# MCU023_XDS110_Debug_Probe.net
KiCad netlist of a schematic drawn in Altium Designer
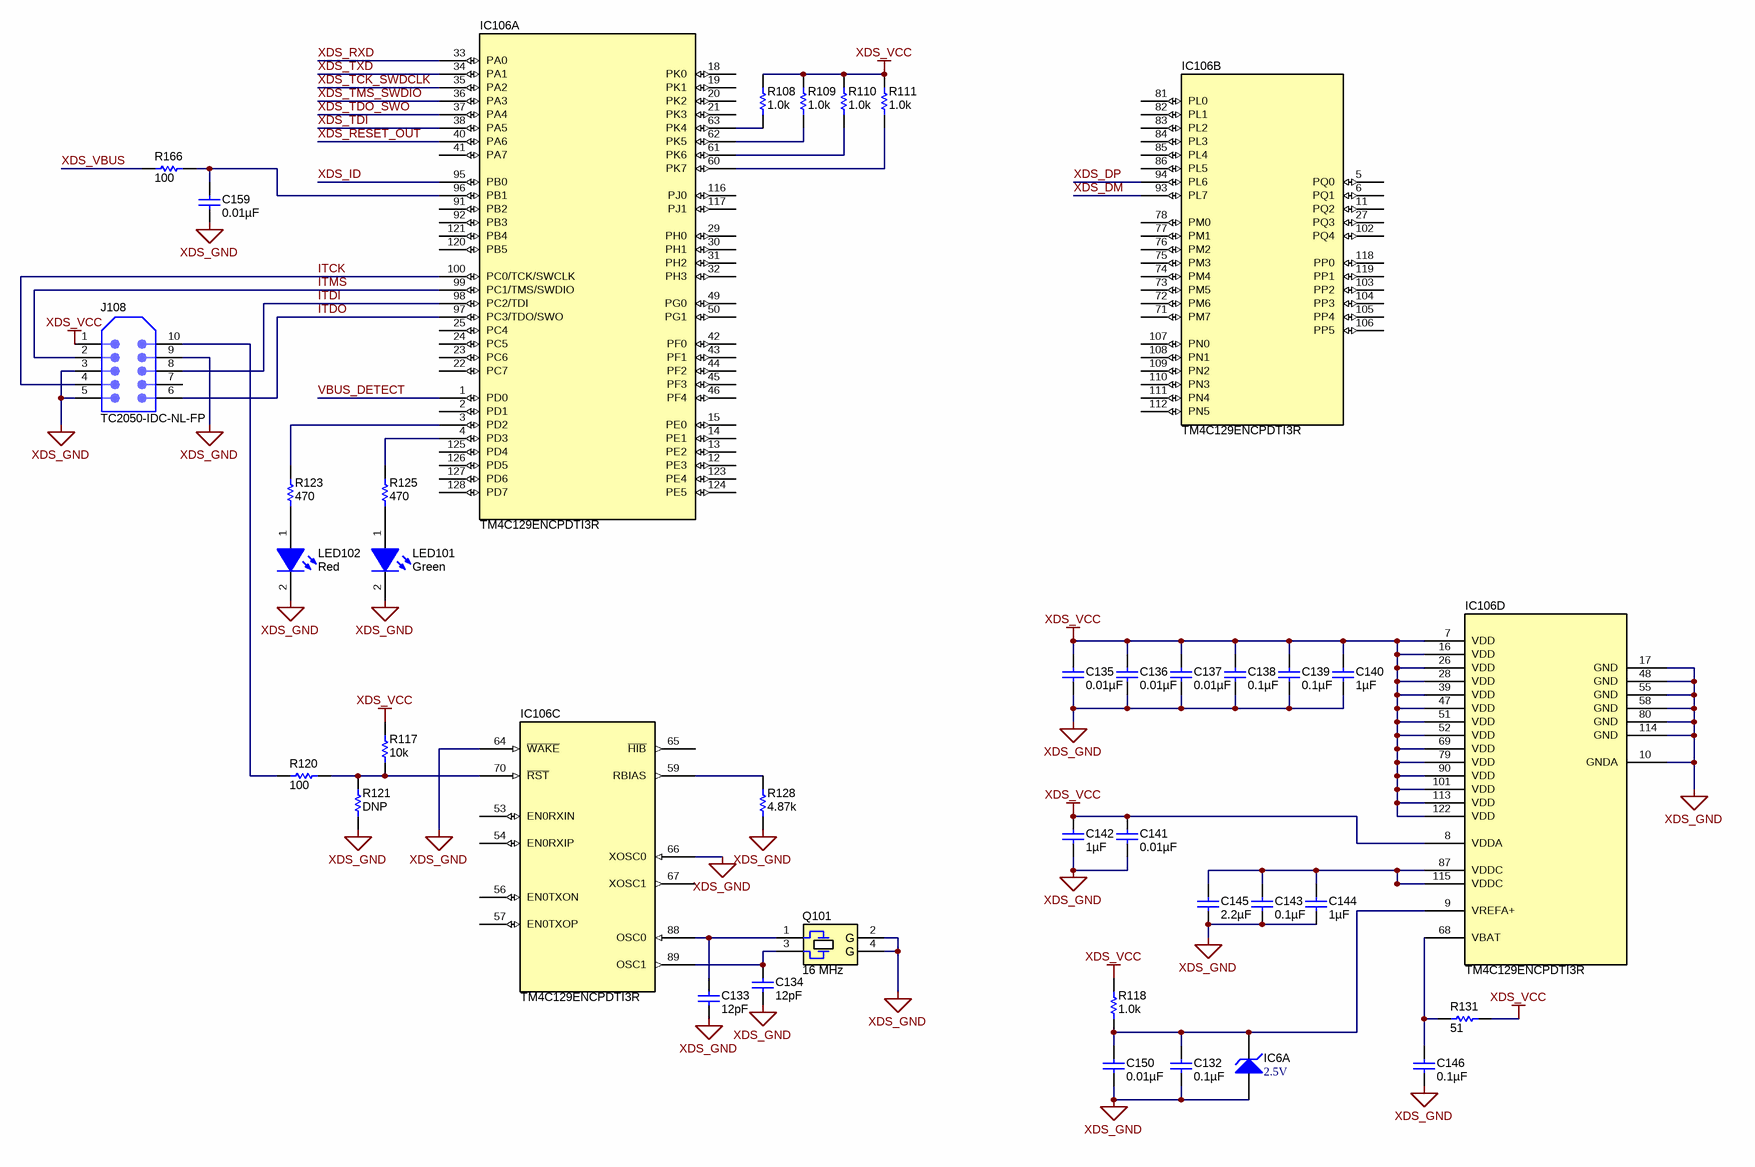
[diagram p0: MCU023_XDS110_Debug_Probe.SchDoc]

(export (version "E")
  (design (tool "Eeschema 10.0.6"))
  (components
    (comp (ref "C132")
      (value "GRM155R70J104KA01D")
      (footprint "0402")
      (description "CAP, CERM, 0.1 µF, 6.3 V, +/- 10%, X7R, 0402")
      (fields
        (field (name "VALUEDISPLAYED") "0.1µF")
        (field (name "MANUFACTURER") "MuRata")
        (field (name "PUBLISHER") "Texas Instruments")
      )
      (libsource (lib "Capacitor_Ceramic") (part "GRM155R70J104KA01D"))
    )
    (comp (ref "C133")
      (value "GRM1555C1H120JA01D")
      (footprint "0402")
      (description "CAP, CERM, 12 pF, 50 V, +/- 5%, C0G/NP0, 0402")
      (fields
        (field (name "VALUEDISPLAYED") "12pF")
        (field (name "MANUFACTURER") "MuRata")
        (field (name "PUBLISHER") "Texas Instruments")
      )
      (libsource (lib "Capacitor_Ceramic") (part "GRM1555C1H120JA01D"))
    )
    (comp (ref "C134")
      (value "GRM1555C1H120JA01D")
      (footprint "0402")
      (description "CAP, CERM, 12 pF, 50 V, +/- 5%, C0G/NP0, 0402")
      (fields
        (field (name "VALUEDISPLAYED") "12pF")
        (field (name "MANUFACTURER") "MuRata")
        (field (name "PUBLISHER") "Texas Instruments")
      )
      (libsource (lib "Capacitor_Ceramic") (part "GRM1555C1H120JA01D"))
    )
    (comp (ref "C135")
      (value "GRM155R71E103KA01D")
      (footprint "0402")
      (description "CAP, CERM, 0.01 µF, 25 V, +/- 10%, X7R, 0402")
      (fields
        (field (name "VALUEDISPLAYED") "0.01µF")
        (field (name "MANUFACTURER") "MuRata")
        (field (name "PUBLISHER") "Texas Instruments")
      )
      (libsource (lib "Capacitor_Ceramic") (part "GRM155R71E103KA01D"))
    )
    (comp (ref "C136")
      (value "GRM155R71E103KA01D")
      (footprint "0402")
      (description "CAP, CERM, 0.01 µF, 25 V, +/- 10%, X7R, 0402")
      (fields
        (field (name "VALUEDISPLAYED") "0.01µF")
        (field (name "MANUFACTURER") "MuRata")
        (field (name "PUBLISHER") "Texas Instruments")
      )
      (libsource (lib "Capacitor_Ceramic") (part "GRM155R71E103KA01D"))
    )
    (comp (ref "C137")
      (value "GRM155R71E103KA01D")
      (footprint "0402")
      (description "CAP, CERM, 0.01 µF, 25 V, +/- 10%, X7R, 0402")
      (fields
        (field (name "VALUEDISPLAYED") "0.01µF")
        (field (name "MANUFACTURER") "MuRata")
        (field (name "PUBLISHER") "Texas Instruments")
      )
      (libsource (lib "Capacitor_Ceramic") (part "GRM155R71E103KA01D"))
    )
    (comp (ref "C138")
      (value "GRM155R70J104KA01D")
      (footprint "0402")
      (description "CAP, CERM, 0.1 µF, 6.3 V, +/- 10%, X7R, 0402")
      (fields
        (field (name "VALUEDISPLAYED") "0.1µF")
        (field (name "MANUFACTURER") "MuRata")
        (field (name "PUBLISHER") "Texas Instruments")
      )
      (libsource (lib "Capacitor_Ceramic") (part "GRM155R70J104KA01D"))
    )
    (comp (ref "C139")
      (value "GRM155R70J104KA01D")
      (footprint "0402")
      (description "CAP, CERM, 0.1 µF, 6.3 V, +/- 10%, X7R, 0402")
      (fields
        (field (name "VALUEDISPLAYED") "0.1µF")
        (field (name "MANUFACTURER") "MuRata")
        (field (name "PUBLISHER") "Texas Instruments")
      )
      (libsource (lib "Capacitor_Ceramic") (part "GRM155R70J104KA01D"))
    )
    (comp (ref "C140")
      (value "GRM155R61A105KE15D")
      (footprint "0402")
      (description "CAP, CERM, 1 µF, 10 V, +/- 10%, X5R, 0402")
      (fields
        (field (name "VALUEDISPLAYED") "1µF")
        (field (name "MANUFACTURER") "MuRata")
        (field (name "PUBLISHER") "Texas Instruments")
      )
      (libsource (lib "Capacitor_Ceramic") (part "GRM155R61A105KE15D"))
    )
    (comp (ref "C141")
      (value "GRM155R71E103KA01D")
      (footprint "0402")
      (description "CAP, CERM, 0.01 µF, 25 V, +/- 10%, X7R, 0402")
      (fields
        (field (name "VALUEDISPLAYED") "0.01µF")
        (field (name "MANUFACTURER") "MuRata")
        (field (name "PUBLISHER") "Texas Instruments")
      )
      (libsource (lib "Capacitor_Ceramic") (part "GRM155R71E103KA01D"))
    )
    (comp (ref "C142")
      (value "GRM155R61A105KE15D")
      (footprint "0402")
      (description "CAP, CERM, 1 µF, 10 V, +/- 10%, X5R, 0402")
      (fields
        (field (name "VALUEDISPLAYED") "1µF")
        (field (name "MANUFACTURER") "MuRata")
        (field (name "PUBLISHER") "Texas Instruments")
      )
      (libsource (lib "Capacitor_Ceramic") (part "GRM155R61A105KE15D"))
    )
    (comp (ref "C143")
      (value "GRM155R70J104KA01D")
      (footprint "0402")
      (description "CAP, CERM, 0.1 µF, 6.3 V, +/- 10%, X7R, 0402")
      (fields
        (field (name "VALUEDISPLAYED") "0.1µF")
        (field (name "MANUFACTURER") "MuRata")
        (field (name "PUBLISHER") "Texas Instruments")
      )
      (libsource (lib "Capacitor_Ceramic") (part "GRM155R70J104KA01D"))
    )
    (comp (ref "C144")
      (value "GRM155R61A105KE15D")
      (footprint "0402")
      (description "CAP, CERM, 1 µF, 10 V, +/- 10%, X5R, 0402")
      (fields
        (field (name "VALUEDISPLAYED") "1µF")
        (field (name "MANUFACTURER") "MuRata")
        (field (name "PUBLISHER") "Texas Instruments")
      )
      (libsource (lib "Capacitor_Ceramic") (part "GRM155R61A105KE15D"))
    )
    (comp (ref "C145")
      (value "GRM155R60J225KE95D")
      (footprint "0402")
      (description "CAP, CERM, 2.2 µF, 6.3 V, +/- 10%, X5R, 0402")
      (fields
        (field (name "VALUEDISPLAYED") "2.2µF")
        (field (name "MANUFACTURER") "MuRata")
        (field (name "PUBLISHER") "Texas Instruments")
      )
      (libsource (lib "Capacitor_Ceramic") (part "GRM155R60J225KE95D"))
    )
    (comp (ref "C146")
      (value "GRM155R70J104KA01D")
      (footprint "0402")
      (description "CAP, CERM, 0.1 µF, 6.3 V, +/- 10%, X7R, 0402")
      (fields
        (field (name "VALUEDISPLAYED") "0.1µF")
        (field (name "MANUFACTURER") "MuRata")
        (field (name "PUBLISHER") "Texas Instruments")
      )
      (libsource (lib "Capacitor_Ceramic") (part "GRM155R70J104KA01D"))
    )
    (comp (ref "C150")
      (value "GRM155R71E103KA01D")
      (footprint "0402")
      (description "CAP, CERM, 0.01 µF, 25 V, +/- 10%, X7R, 0402")
      (fields
        (field (name "VALUEDISPLAYED") "0.01µF")
        (field (name "MANUFACTURER") "MuRata")
        (field (name "PUBLISHER") "Texas Instruments")
      )
      (libsource (lib "Capacitor_Ceramic") (part "GRM155R71E103KA01D"))
    )
    (comp (ref "C159")
      (value "GRM155R71E103KA01D")
      (footprint "0402")
      (description "CAP, CERM, 0.01 µF, 25 V, +/- 10%, X7R, 0402")
      (fields
        (field (name "VALUEDISPLAYED") "0.01µF")
        (field (name "MANUFACTURER") "MuRata")
        (field (name "PUBLISHER") "Texas Instruments")
      )
      (libsource (lib "Capacitor_Ceramic") (part "GRM155R71E103KA01D"))
    )
    (comp (ref "IC6")
      (value "2.5V")
      (footprint "DCK0005A_N")
      (fields
        (field (name "MANUFACTURER") "Texas Instruments")
        (field (name "ALTERNATE PARTNUMBER") "Equivalent")
        (field (name "PARTNUMBER") "LM4040B25IDCKRA")
      )
      (libsource (lib "TI Power Management Shunt Voltage Reference") (part "LM4040B25IDCKR"))
    )
    (comp (ref "IC106")
      (value "TM4C129ENCPDTI3R")
      (footprint "PDT0128A")
      (description "IoT enabled High performance 32-bit ARM(R) Cortex(R)-M4F based MCU, PDT0128A (TQFP-128)")
      (fields
        (field (name "ALTERNATE PARTNUMBER") "TM4C129ENCPDTI3")
        (field (name "MANUFACTURER") "Texas Instruments")
        (field (name "SYMBOLCREATOR") "a0411947")
        (field (name "PUBLISHER") "Texas Instruments")
      )
      (libsource (lib "TI_Pre_Release") (part "TM4C129ENCPDTI3R"))
    )
    (comp (ref "J108")
      (value "TC2050-IDC-NL-FP")
      (footprint "Tag_TC2050-NL")
      (description "Footprint for Tag-Connect TC2050 No-Legs cables")
      (fields
        (field (name "MANUFACTURER") "Tag-Connect")
        (field (name "SYMBOLCREATOR") "Altium")
        (field (name "PUBLISHER") "Texas Instruments")
      )
      (libsource (lib "Connectors_Other") (part "TC2050-IDC-NL-FP"))
    )
    (comp (ref "LED101")
      (value "Green")
      (footprint "LED_LTST-C190")
      (description "LED, Green, SMD")
      (fields
        (field (name "PARTNUMBER") "LTST-C190GKT")
        (field (name "MANUFACTURER") "Lite-On")
        (field (name "PUBLISHER") "Texas Instruments")
      )
      (libsource (lib "LED") (part "LTST-C190GKT"))
    )
    (comp (ref "LED102")
      (value "Red")
      (footprint "LED_LTST-C190_Red")
      (description "LED, Red, SMD")
      (fields
        (field (name "PARTNUMBER") "LTST-C190CKT")
        (field (name "MANUFACTURER") "Lite-On")
        (field (name "PUBLISHER") "Texas Instruments")
      )
      (libsource (lib "LED") (part "LTST-C190CKT"))
    )
    (comp (ref "Q101")
      (value "NX3225GA-16.000M-STD-CRG-1")
      (footprint "NDK_NX3225GA")
      (description "Crystal, 16MHz, 8pF, SMD")
      (fields
        (field (name "FREQUENCY") "16 MHz")
        (field (name "MANUFACTURER") "NDK")
        (field (name "SYMBOLCREATOR") "a0412235")
        (field (name "PUBLISHER") "Texas Instruments")
      )
      (libsource (lib "Oscillators") (part "NX3225GA-16.000M-STD-CRG-1"))
    )
    (comp (ref "R108")
      (value "CRCW04021K00JNED")
      (footprint "0402")
      (description "RES, 1.0 k, 5%, 0.063 W, 0402")
      (fields
        (field (name "VALUEDISPLAYED") "1.0k")
        (field (name "MANUFACTURER") "Vishay-Dale")
        (field (name "PUBLISHER") "Texas Instruments")
      )
      (libsource (lib "Resistor_0402") (part "CRCW04021K00JNED"))
    )
    (comp (ref "R109")
      (value "CRCW04021K00JNED")
      (footprint "0402")
      (description "RES, 1.0 k, 5%, 0.063 W, 0402")
      (fields
        (field (name "VALUEDISPLAYED") "1.0k")
        (field (name "MANUFACTURER") "Vishay-Dale")
        (field (name "PUBLISHER") "Texas Instruments")
      )
      (libsource (lib "Resistor_0402") (part "CRCW04021K00JNED"))
    )
    (comp (ref "R110")
      (value "CRCW04021K00JNED")
      (footprint "0402")
      (description "RES, 1.0 k, 5%, 0.063 W, 0402")
      (fields
        (field (name "VALUEDISPLAYED") "1.0k")
        (field (name "MANUFACTURER") "Vishay-Dale")
        (field (name "PUBLISHER") "Texas Instruments")
      )
      (libsource (lib "Resistor_0402") (part "CRCW04021K00JNED"))
    )
    (comp (ref "R111")
      (value "CRCW04021K00JNED")
      (footprint "0402")
      (description "RES, 1.0 k, 5%, 0.063 W, 0402")
      (fields
        (field (name "VALUEDISPLAYED") "1.0k")
        (field (name "MANUFACTURER") "Vishay-Dale")
        (field (name "PUBLISHER") "Texas Instruments")
      )
      (libsource (lib "Resistor_0402") (part "CRCW04021K00JNED"))
    )
    (comp (ref "R117")
      (value "CRCW040210K0JNED")
      (footprint "0402")
      (description "RES, 10 k, 5%, 0.063 W, 0402")
      (fields
        (field (name "VALUEDISPLAYED") "10k")
        (field (name "MANUFACTURER") "Vishay-Dale")
        (field (name "PUBLISHER") "Texas Instruments")
      )
      (libsource (lib "Resistor_0402") (part "CRCW040210K0JNED"))
    )
    (comp (ref "R118")
      (value "CRCW04021K00JNED")
      (footprint "0402")
      (description "RES, 1.0 k, 5%, 0.063 W, 0402")
      (fields
        (field (name "VALUEDISPLAYED") "1.0k")
        (field (name "MANUFACTURER") "Vishay-Dale")
        (field (name "PUBLISHER") "Texas Instruments")
      )
      (libsource (lib "Resistor_0402") (part "CRCW04021K00JNED"))
    )
    (comp (ref "R120")
      (value "CRCW0402100RJNED")
      (footprint "0402")
      (description "RES, 100, 5%, 0.063 W, 0402")
      (fields
        (field (name "VALUEDISPLAYED") "100")
        (field (name "MANUFACTURER") "Vishay-Dale")
        (field (name "PUBLISHER") "Texas Instruments")
      )
      (libsource (lib "Resistor_0402") (part "CRCW0402100RJNED"))
    )
    (comp (ref "R121")
      (value "CRCW040210K0JNED")
      (footprint "0402")
      (description "RES, 10 k, 5%, 0.063 W, 0402")
      (fields
        (field (name "VALUEDISPLAYED") "DNP")
        (field (name "MANUFACTURER") "Vishay-Dale")
        (field (name "PUBLISHER") "Texas Instruments")
      )
      (libsource (lib "Resistor_0402") (part "CRCW040210K0JNED"))
    )
    (comp (ref "R123")
      (value "ERJ-2RKF4700X")
      (footprint "0402")
      (description "RES, 470, 1%, 0.1 W, AEC-Q200 Grade 0, 0402")
      (fields
        (field (name "VALUEDISPLAYED") "470")
        (field (name "MANUFACTURER") "Panasonic")
        (field (name "PUBLISHER") "Texas Instruments")
      )
      (libsource (lib "Resistor_0402") (part "ERJ-2RKF4700X"))
    )
    (comp (ref "R125")
      (value "ERJ-2RKF4700X")
      (footprint "0402")
      (description "RES, 470, 1%, 0.1 W, AEC-Q200 Grade 0, 0402")
      (fields
        (field (name "VALUEDISPLAYED") "470")
        (field (name "MANUFACTURER") "Panasonic")
        (field (name "PUBLISHER") "Texas Instruments")
      )
      (libsource (lib "Resistor_0402") (part "ERJ-2RKF4700X"))
    )
    (comp (ref "R128")
      (value "CRCW04024K87FKED")
      (footprint "0402")
      (description "RES, 4.87 k, 1%, 0.063 W, 0402")
      (fields
        (field (name "VALUEDISPLAYED") "4.87k")
        (field (name "MANUFACTURER") "Vishay-Dale")
        (field (name "PUBLISHER") "Texas Instruments")
      )
      (libsource (lib "Resistor_0402") (part "CRCW04024K87FKED"))
    )
    (comp (ref "R131")
      (value "CRCW040251R0JNED")
      (footprint "0402")
      (description "RES, 51, 5%, 0.063 W, 0402")
      (fields
        (field (name "VALUEDISPLAYED") "51")
        (field (name "MANUFACTURER") "Vishay-Dale")
        (field (name "PUBLISHER") "Texas Instruments")
      )
      (libsource (lib "Resistor_0402") (part "CRCW040251R0JNED"))
    )
    (comp (ref "R166")
      (value "CRCW0402100RJNED")
      (footprint "0402")
      (description "RES, 100, 5%, 0.063 W, 0402")
      (fields
        (field (name "VALUEDISPLAYED") "100")
        (field (name "MANUFACTURER") "Vishay-Dale")
        (field (name "PUBLISHER") "Texas Instruments")
      )
      (libsource (lib "Resistor_0402") (part "CRCW0402100RJNED"))
    )
  )
  (nets
    (net (code "1") (name "/ITCK") (class "Default")
      (node (ref "IC106") (pin "100") (pinfunction "PC0/TCK/SWCLK_100") (pintype "bidirectional"))
      (node (ref "J108") (pin "4") (pinfunction "4_4") (pintype "passive"))
    )
    (net (code "2") (name "/ITDI") (class "Default")
      (node (ref "IC106") (pin "98") (pinfunction "PC2/TDI_98") (pintype "bidirectional"))
      (node (ref "J108") (pin "8") (pinfunction "8_8") (pintype "passive"))
    )
    (net (code "3") (name "/ITDO") (class "Default")
      (node (ref "IC106") (pin "97") (pinfunction "PC3/TDO/SWO_97") (pintype "bidirectional"))
      (node (ref "J108") (pin "6") (pinfunction "6_6") (pintype "passive"))
    )
    (net (code "4") (name "/ITMS") (class "Default")
      (node (ref "IC106") (pin "99") (pinfunction "PC1/TMS/SWDIO_99") (pintype "bidirectional"))
      (node (ref "J108") (pin "2") (pinfunction "2_2") (pintype "passive"))
    )
    (net (code "5") (name "/VBUS_DETECT") (class "Default")
      (node (ref "IC106") (pin "1") (pinfunction "PD0_1") (pintype "bidirectional"))
    )
    (net (code "6") (name "/XDS_DM") (class "Default")
      (node (ref "IC106") (pin "93") (pinfunction "PL7_93") (pintype "bidirectional"))
    )
    (net (code "7") (name "/XDS_DP") (class "Default")
      (node (ref "IC106") (pin "94") (pinfunction "PL6_94") (pintype "bidirectional"))
    )
    (net (code "8") (name "/XDS_ID") (class "Default")
      (node (ref "IC106") (pin "95") (pinfunction "PB0_95") (pintype "bidirectional"))
    )
    (net (code "9") (name "/XDS_RESET_OUT") (class "Default")
      (node (ref "IC106") (pin "40") (pinfunction "PA6_40") (pintype "bidirectional"))
    )
    (net (code "10") (name "/XDS_RXD") (class "Default")
      (node (ref "IC106") (pin "33") (pinfunction "PA0_33") (pintype "bidirectional"))
    )
    (net (code "11") (name "/XDS_TCK_SWDCLK") (class "Default")
      (node (ref "IC106") (pin "35") (pinfunction "PA2_35") (pintype "bidirectional"))
    )
    (net (code "12") (name "/XDS_TDI") (class "Default")
      (node (ref "IC106") (pin "38") (pinfunction "PA5_38") (pintype "bidirectional"))
    )
    (net (code "13") (name "/XDS_TDO_SWO") (class "Default")
      (node (ref "IC106") (pin "37") (pinfunction "PA4_37") (pintype "bidirectional"))
    )
    (net (code "14") (name "/XDS_TMS_SWDIO") (class "Default")
      (node (ref "IC106") (pin "36") (pinfunction "PA3_36") (pintype "bidirectional"))
    )
    (net (code "15") (name "/XDS_TXD") (class "Default")
      (node (ref "IC106") (pin "34") (pinfunction "PA1_34") (pintype "bidirectional"))
    )
    (net (code "16") (name "/XDS_VBUS") (class "Default")
      (node (ref "R166") (pin "1") (pinfunction "1_1") (pintype "passive"))
    )
    (net (code "17") (name "Net-(C143-Pad1)") (class "Default")
      (node (ref "C143") (pin "1") (pinfunction "1_1") (pintype "passive"))
      (node (ref "C144") (pin "1") (pinfunction "1_1") (pintype "passive"))
      (node (ref "C145") (pin "1") (pinfunction "1_1") (pintype "passive"))
      (node (ref "IC106") (pin "115") (pinfunction "VDDC_115") (pintype "power_in"))
      (node (ref "IC106") (pin "87") (pinfunction "VDDC_87") (pintype "power_in"))
    )
    (net (code "18") (name "Net-(IC106A-PB1)") (class "Default")
      (node (ref "C159") (pin "1") (pinfunction "1_1") (pintype "passive"))
      (node (ref "IC106") (pin "96") (pinfunction "PB1_96") (pintype "bidirectional"))
      (node (ref "R166") (pin "2") (pinfunction "2_2") (pintype "passive"))
    )
    (net (code "19") (name "Net-(IC106A-PD2)") (class "Default")
      (node (ref "IC106") (pin "3") (pinfunction "PD2_3") (pintype "bidirectional"))
      (node (ref "R123") (pin "2") (pinfunction "2_2") (pintype "passive"))
    )
    (net (code "20") (name "Net-(IC106A-PD3)") (class "Default")
      (node (ref "IC106") (pin "4") (pinfunction "PD3_4") (pintype "bidirectional"))
      (node (ref "R125") (pin "2") (pinfunction "2_2") (pintype "passive"))
    )
    (net (code "21") (name "Net-(IC106A-PK4)") (class "Default")
      (node (ref "IC106") (pin "63") (pinfunction "PK4_63") (pintype "bidirectional"))
      (node (ref "R108") (pin "1") (pinfunction "1_1") (pintype "passive"))
    )
    (net (code "22") (name "Net-(IC106A-PK5)") (class "Default")
      (node (ref "IC106") (pin "62") (pinfunction "PK5_62") (pintype "bidirectional"))
      (node (ref "R109") (pin "1") (pinfunction "1_1") (pintype "passive"))
    )
    (net (code "23") (name "Net-(IC106A-PK6)") (class "Default")
      (node (ref "IC106") (pin "61") (pinfunction "PK6_61") (pintype "bidirectional"))
      (node (ref "R110") (pin "1") (pinfunction "1_1") (pintype "passive"))
    )
    (net (code "24") (name "Net-(IC106A-PK7)") (class "Default")
      (node (ref "IC106") (pin "60") (pinfunction "PK7_60") (pintype "bidirectional"))
      (node (ref "R111") (pin "1") (pinfunction "1_1") (pintype "passive"))
    )
    (net (code "25") (name "Net-(IC106C-OSC0)") (class "Default")
      (node (ref "C133") (pin "1") (pinfunction "1_1") (pintype "passive"))
      (node (ref "IC106") (pin "88") (pinfunction "OSC0_88") (pintype "input"))
      (node (ref "Q101") (pin "1") (pinfunction "1_1") (pintype "passive"))
    )
    (net (code "26") (name "Net-(IC106C-OSC1)") (class "Default")
      (node (ref "C134") (pin "1") (pinfunction "1_1") (pintype "passive"))
      (node (ref "IC106") (pin "89") (pinfunction "OSC1_89") (pintype "output"))
      (node (ref "Q101") (pin "3") (pinfunction "3_3") (pintype "passive"))
    )
    (net (code "27") (name "Net-(IC106C-RBIAS)") (class "Default")
      (node (ref "IC106") (pin "59") (pinfunction "RBIAS_59") (pintype "output"))
      (node (ref "R128") (pin "2") (pinfunction "2_2") (pintype "passive"))
    )
    (net (code "28") (name "Net-(IC106C-RST)") (class "Default")
      (node (ref "IC106") (pin "70") (pinfunction "RST_70") (pintype "input"))
      (node (ref "R117") (pin "1") (pinfunction "1_1") (pintype "passive"))
      (node (ref "R120") (pin "2") (pinfunction "2_2") (pintype "passive"))
      (node (ref "R121") (pin "2") (pinfunction "2_2") (pintype "passive"))
    )
    (net (code "29") (name "Net-(IC106D-VBAT)") (class "Default")
      (node (ref "C146") (pin "1") (pinfunction "1_1") (pintype "passive"))
      (node (ref "IC106") (pin "68") (pinfunction "VBAT_68") (pintype "power_in"))
      (node (ref "R131") (pin "1") (pinfunction "1_1") (pintype "passive"))
    )
    (net (code "30") (name "Net-(IC106D-VREFA+)") (class "Default")
      (node (ref "C132") (pin "1") (pinfunction "1_1") (pintype "passive"))
      (node (ref "C150") (pin "1") (pinfunction "1_1") (pintype "passive"))
      (node (ref "IC106") (pin "9") (pinfunction "VREFA+_9") (pintype "power_in"))
      (node (ref "IC6") (pin "3") (pinfunction "CATHODE_3") (pintype "passive"))
      (node (ref "R118") (pin "1") (pinfunction "1_1") (pintype "passive"))
    )
    (net (code "31") (name "Net-(J108-Pad10)") (class "Default")
      (node (ref "J108") (pin "10") (pinfunction "10_10") (pintype "passive"))
      (node (ref "R120") (pin "1") (pinfunction "1_1") (pintype "passive"))
    )
    (net (code "32") (name "Net-(LED101-A)") (class "Default")
      (node (ref "LED101") (pin "1") (pinfunction "A_1") (pintype "passive"))
      (node (ref "R125") (pin "1") (pinfunction "1_1") (pintype "passive"))
    )
    (net (code "33") (name "Net-(LED102-A)") (class "Default")
      (node (ref "LED102") (pin "1") (pinfunction "A_1") (pintype "passive"))
      (node (ref "R123") (pin "1") (pinfunction "1_1") (pintype "passive"))
    )
    (net (code "34") (name "XDS_GND") (class "Default")
      (node (ref "C132") (pin "2") (pinfunction "2_2") (pintype "passive"))
      (node (ref "C133") (pin "2") (pinfunction "2_2") (pintype "passive"))
      (node (ref "C134") (pin "2") (pinfunction "2_2") (pintype "passive"))
      (node (ref "C135") (pin "2") (pinfunction "2_2") (pintype "passive"))
      (node (ref "C136") (pin "2") (pinfunction "2_2") (pintype "passive"))
      (node (ref "C137") (pin "2") (pinfunction "2_2") (pintype "passive"))
      (node (ref "C138") (pin "2") (pinfunction "2_2") (pintype "passive"))
      (node (ref "C139") (pin "2") (pinfunction "2_2") (pintype "passive"))
      (node (ref "C140") (pin "2") (pinfunction "2_2") (pintype "passive"))
      (node (ref "C141") (pin "2") (pinfunction "2_2") (pintype "passive"))
      (node (ref "C142") (pin "2") (pinfunction "2_2") (pintype "passive"))
      (node (ref "C143") (pin "2") (pinfunction "2_2") (pintype "passive"))
      (node (ref "C144") (pin "2") (pinfunction "2_2") (pintype "passive"))
      (node (ref "C145") (pin "2") (pinfunction "2_2") (pintype "passive"))
      (node (ref "C146") (pin "2") (pinfunction "2_2") (pintype "passive"))
      (node (ref "C150") (pin "2") (pinfunction "2_2") (pintype "passive"))
      (node (ref "C159") (pin "2") (pinfunction "2_2") (pintype "passive"))
      (node (ref "IC106") (pin "10") (pinfunction "GNDA_10") (pintype "power_in"))
      (node (ref "IC106") (pin "114") (pinfunction "GND_114") (pintype "power_in"))
      (node (ref "IC106") (pin "17") (pinfunction "GND_17") (pintype "power_in"))
      (node (ref "IC106") (pin "48") (pinfunction "GND_48") (pintype "power_in"))
      (node (ref "IC106") (pin "55") (pinfunction "GND_55") (pintype "power_in"))
      (node (ref "IC106") (pin "58") (pinfunction "GND_58") (pintype "power_in"))
      (node (ref "IC106") (pin "64") (pinfunction "WAKE_64") (pintype "input"))
      (node (ref "IC106") (pin "66") (pinfunction "XOSC0_66") (pintype "input"))
      (node (ref "IC106") (pin "80") (pinfunction "GND_80") (pintype "power_in"))
      (node (ref "IC6") (pin "1") (pinfunction "ANODE_1") (pintype "passive"))
      (node (ref "J108") (pin "3") (pinfunction "3_3") (pintype "passive"))
      (node (ref "J108") (pin "5") (pinfunction "5_5") (pintype "passive"))
      (node (ref "J108") (pin "9") (pinfunction "9_9") (pintype "passive"))
      (node (ref "LED101") (pin "2") (pinfunction "K_2") (pintype "passive"))
      (node (ref "LED102") (pin "2") (pinfunction "K_2") (pintype "passive"))
      (node (ref "Q101") (pin "2") (pinfunction "GND_2") (pintype "power_in"))
      (node (ref "Q101") (pin "4") (pinfunction "GND_4") (pintype "power_in"))
      (node (ref "R121") (pin "1") (pinfunction "1_1") (pintype "passive"))
      (node (ref "R128") (pin "1") (pinfunction "1_1") (pintype "passive"))
    )
    (net (code "35") (name "XDS_VCC") (class "Default")
      (node (ref "C135") (pin "1") (pinfunction "1_1") (pintype "passive"))
      (node (ref "C136") (pin "1") (pinfunction "1_1") (pintype "passive"))
      (node (ref "C137") (pin "1") (pinfunction "1_1") (pintype "passive"))
      (node (ref "C138") (pin "1") (pinfunction "1_1") (pintype "passive"))
      (node (ref "C139") (pin "1") (pinfunction "1_1") (pintype "passive"))
      (node (ref "C140") (pin "1") (pinfunction "1_1") (pintype "passive"))
      (node (ref "C141") (pin "1") (pinfunction "1_1") (pintype "passive"))
      (node (ref "C142") (pin "1") (pinfunction "1_1") (pintype "passive"))
      (node (ref "IC106") (pin "101") (pinfunction "VDD_101") (pintype "power_in"))
      (node (ref "IC106") (pin "113") (pinfunction "VDD_113") (pintype "power_in"))
      (node (ref "IC106") (pin "122") (pinfunction "VDD_122") (pintype "power_in"))
      (node (ref "IC106") (pin "16") (pinfunction "VDD_16") (pintype "power_in"))
      (node (ref "IC106") (pin "26") (pinfunction "VDD_26") (pintype "power_in"))
      (node (ref "IC106") (pin "28") (pinfunction "VDD_28") (pintype "power_in"))
      (node (ref "IC106") (pin "39") (pinfunction "VDD_39") (pintype "power_in"))
      (node (ref "IC106") (pin "47") (pinfunction "VDD_47") (pintype "power_in"))
      (node (ref "IC106") (pin "51") (pinfunction "VDD_51") (pintype "power_in"))
      (node (ref "IC106") (pin "52") (pinfunction "VDD_52") (pintype "power_in"))
      (node (ref "IC106") (pin "69") (pinfunction "VDD_69") (pintype "power_in"))
      (node (ref "IC106") (pin "7") (pinfunction "VDD_7") (pintype "power_in"))
      (node (ref "IC106") (pin "79") (pinfunction "VDD_79") (pintype "power_in"))
      (node (ref "IC106") (pin "8") (pinfunction "VDDA_8") (pintype "power_in"))
      (node (ref "IC106") (pin "90") (pinfunction "VDD_90") (pintype "power_in"))
      (node (ref "J108") (pin "1") (pinfunction "1_1") (pintype "passive"))
      (node (ref "R108") (pin "2") (pinfunction "2_2") (pintype "passive"))
      (node (ref "R109") (pin "2") (pinfunction "2_2") (pintype "passive"))
      (node (ref "R110") (pin "2") (pinfunction "2_2") (pintype "passive"))
      (node (ref "R111") (pin "2") (pinfunction "2_2") (pintype "passive"))
      (node (ref "R117") (pin "2") (pinfunction "2_2") (pintype "passive"))
      (node (ref "R118") (pin "2") (pinfunction "2_2") (pintype "passive"))
      (node (ref "R131") (pin "2") (pinfunction "2_2") (pintype "passive"))
    )
    (net (code "36") (name "unconnected-(IC106A-PA7-Pad41)") (class "Default")
      (node (ref "IC106") (pin "41") (pinfunction "PA7_41") (pintype "bidirectional"))
    )
    (net (code "37") (name "unconnected-(IC106A-PB2-Pad91)") (class "Default")
      (node (ref "IC106") (pin "91") (pinfunction "PB2_91") (pintype "bidirectional"))
    )
    (net (code "38") (name "unconnected-(IC106A-PB3-Pad92)") (class "Default")
      (node (ref "IC106") (pin "92") (pinfunction "PB3_92") (pintype "bidirectional"))
    )
    (net (code "39") (name "unconnected-(IC106A-PB4-Pad121)") (class "Default")
      (node (ref "IC106") (pin "121") (pinfunction "PB4_121") (pintype "bidirectional"))
    )
    (net (code "40") (name "unconnected-(IC106A-PB5-Pad120)") (class "Default")
      (node (ref "IC106") (pin "120") (pinfunction "PB5_120") (pintype "bidirectional"))
    )
    (net (code "41") (name "unconnected-(IC106A-PC4-Pad25)") (class "Default")
      (node (ref "IC106") (pin "25") (pinfunction "PC4_25") (pintype "bidirectional"))
    )
    (net (code "42") (name "unconnected-(IC106A-PC5-Pad24)") (class "Default")
      (node (ref "IC106") (pin "24") (pinfunction "PC5_24") (pintype "bidirectional"))
    )
    (net (code "43") (name "unconnected-(IC106A-PC6-Pad23)") (class "Default")
      (node (ref "IC106") (pin "23") (pinfunction "PC6_23") (pintype "bidirectional"))
    )
    (net (code "44") (name "unconnected-(IC106A-PC7-Pad22)") (class "Default")
      (node (ref "IC106") (pin "22") (pinfunction "PC7_22") (pintype "bidirectional"))
    )
    (net (code "45") (name "unconnected-(IC106A-PD1-Pad2)") (class "Default")
      (node (ref "IC106") (pin "2") (pinfunction "PD1_2") (pintype "bidirectional"))
    )
    (net (code "46") (name "unconnected-(IC106A-PD4-Pad125)") (class "Default")
      (node (ref "IC106") (pin "125") (pinfunction "PD4_125") (pintype "bidirectional"))
    )
    (net (code "47") (name "unconnected-(IC106A-PD5-Pad126)") (class "Default")
      (node (ref "IC106") (pin "126") (pinfunction "PD5_126") (pintype "bidirectional"))
    )
    (net (code "48") (name "unconnected-(IC106A-PD6-Pad127)") (class "Default")
      (node (ref "IC106") (pin "127") (pinfunction "PD6_127") (pintype "bidirectional"))
    )
    (net (code "49") (name "unconnected-(IC106A-PD7-Pad128)") (class "Default")
      (node (ref "IC106") (pin "128") (pinfunction "PD7_128") (pintype "bidirectional"))
    )
    (net (code "50") (name "unconnected-(IC106A-PE0-Pad15)") (class "Default")
      (node (ref "IC106") (pin "15") (pinfunction "PE0_15") (pintype "bidirectional"))
    )
    (net (code "51") (name "unconnected-(IC106A-PE1-Pad14)") (class "Default")
      (node (ref "IC106") (pin "14") (pinfunction "PE1_14") (pintype "bidirectional"))
    )
    (net (code "52") (name "unconnected-(IC106A-PE2-Pad13)") (class "Default")
      (node (ref "IC106") (pin "13") (pinfunction "PE2_13") (pintype "bidirectional"))
    )
    (net (code "53") (name "unconnected-(IC106A-PE3-Pad12)") (class "Default")
      (node (ref "IC106") (pin "12") (pinfunction "PE3_12") (pintype "bidirectional"))
    )
    (net (code "54") (name "unconnected-(IC106A-PE4-Pad123)") (class "Default")
      (node (ref "IC106") (pin "123") (pinfunction "PE4_123") (pintype "bidirectional"))
    )
    (net (code "55") (name "unconnected-(IC106A-PE5-Pad124)") (class "Default")
      (node (ref "IC106") (pin "124") (pinfunction "PE5_124") (pintype "bidirectional"))
    )
    (net (code "56") (name "unconnected-(IC106A-PF0-Pad42)") (class "Default")
      (node (ref "IC106") (pin "42") (pinfunction "PF0_42") (pintype "bidirectional"))
    )
    (net (code "57") (name "unconnected-(IC106A-PF1-Pad43)") (class "Default")
      (node (ref "IC106") (pin "43") (pinfunction "PF1_43") (pintype "bidirectional"))
    )
    (net (code "58") (name "unconnected-(IC106A-PF2-Pad44)") (class "Default")
      (node (ref "IC106") (pin "44") (pinfunction "PF2_44") (pintype "bidirectional"))
    )
    (net (code "59") (name "unconnected-(IC106A-PF3-Pad45)") (class "Default")
      (node (ref "IC106") (pin "45") (pinfunction "PF3_45") (pintype "bidirectional"))
    )
    (net (code "60") (name "unconnected-(IC106A-PF4-Pad46)") (class "Default")
      (node (ref "IC106") (pin "46") (pinfunction "PF4_46") (pintype "bidirectional"))
    )
    (net (code "61") (name "unconnected-(IC106A-PG0-Pad49)") (class "Default")
      (node (ref "IC106") (pin "49") (pinfunction "PG0_49") (pintype "bidirectional"))
    )
    (net (code "62") (name "unconnected-(IC106A-PG1-Pad50)") (class "Default")
      (node (ref "IC106") (pin "50") (pinfunction "PG1_50") (pintype "bidirectional"))
    )
    (net (code "63") (name "unconnected-(IC106A-PH0-Pad29)") (class "Default")
      (node (ref "IC106") (pin "29") (pinfunction "PH0_29") (pintype "bidirectional"))
    )
    (net (code "64") (name "unconnected-(IC106A-PH1-Pad30)") (class "Default")
      (node (ref "IC106") (pin "30") (pinfunction "PH1_30") (pintype "bidirectional"))
    )
    (net (code "65") (name "unconnected-(IC106A-PH2-Pad31)") (class "Default")
      (node (ref "IC106") (pin "31") (pinfunction "PH2_31") (pintype "bidirectional"))
    )
    (net (code "66") (name "unconnected-(IC106A-PH3-Pad32)") (class "Default")
      (node (ref "IC106") (pin "32") (pinfunction "PH3_32") (pintype "bidirectional"))
    )
    (net (code "67") (name "unconnected-(IC106A-PJ0-Pad116)") (class "Default")
      (node (ref "IC106") (pin "116") (pinfunction "PJ0_116") (pintype "bidirectional"))
    )
    (net (code "68") (name "unconnected-(IC106A-PJ1-Pad117)") (class "Default")
      (node (ref "IC106") (pin "117") (pinfunction "PJ1_117") (pintype "bidirectional"))
    )
    (net (code "69") (name "unconnected-(IC106A-PK0-Pad18)") (class "Default")
      (node (ref "IC106") (pin "18") (pinfunction "PK0_18") (pintype "bidirectional"))
    )
    (net (code "70") (name "unconnected-(IC106A-PK1-Pad19)") (class "Default")
      (node (ref "IC106") (pin "19") (pinfunction "PK1_19") (pintype "bidirectional"))
    )
    (net (code "71") (name "unconnected-(IC106A-PK2-Pad20)") (class "Default")
      (node (ref "IC106") (pin "20") (pinfunction "PK2_20") (pintype "bidirectional"))
    )
    (net (code "72") (name "unconnected-(IC106A-PK3-Pad21)") (class "Default")
      (node (ref "IC106") (pin "21") (pinfunction "PK3_21") (pintype "bidirectional"))
    )
    (net (code "73") (name "unconnected-(IC106B-PL0-Pad81)") (class "Default")
      (node (ref "IC106") (pin "81") (pinfunction "PL0_81") (pintype "bidirectional"))
    )
    (net (code "74") (name "unconnected-(IC106B-PL1-Pad82)") (class "Default")
      (node (ref "IC106") (pin "82") (pinfunction "PL1_82") (pintype "bidirectional"))
    )
    (net (code "75") (name "unconnected-(IC106B-PL2-Pad83)") (class "Default")
      (node (ref "IC106") (pin "83") (pinfunction "PL2_83") (pintype "bidirectional"))
    )
    (net (code "76") (name "unconnected-(IC106B-PL3-Pad84)") (class "Default")
      (node (ref "IC106") (pin "84") (pinfunction "PL3_84") (pintype "bidirectional"))
    )
    (net (code "77") (name "unconnected-(IC106B-PL4-Pad85)") (class "Default")
      (node (ref "IC106") (pin "85") (pinfunction "PL4_85") (pintype "bidirectional"))
    )
    (net (code "78") (name "unconnected-(IC106B-PL5-Pad86)") (class "Default")
      (node (ref "IC106") (pin "86") (pinfunction "PL5_86") (pintype "bidirectional"))
    )
    (net (code "79") (name "unconnected-(IC106B-PM0-Pad78)") (class "Default")
      (node (ref "IC106") (pin "78") (pinfunction "PM0_78") (pintype "bidirectional"))
    )
    (net (code "80") (name "unconnected-(IC106B-PM1-Pad77)") (class "Default")
      (node (ref "IC106") (pin "77") (pinfunction "PM1_77") (pintype "bidirectional"))
    )
    (net (code "81") (name "unconnected-(IC106B-PM2-Pad76)") (class "Default")
      (node (ref "IC106") (pin "76") (pinfunction "PM2_76") (pintype "bidirectional"))
    )
    (net (code "82") (name "unconnected-(IC106B-PM3-Pad75)") (class "Default")
      (node (ref "IC106") (pin "75") (pinfunction "PM3_75") (pintype "bidirectional"))
    )
    (net (code "83") (name "unconnected-(IC106B-PM4-Pad74)") (class "Default")
      (node (ref "IC106") (pin "74") (pinfunction "PM4_74") (pintype "bidirectional"))
    )
    (net (code "84") (name "unconnected-(IC106B-PM5-Pad73)") (class "Default")
      (node (ref "IC106") (pin "73") (pinfunction "PM5_73") (pintype "bidirectional"))
    )
    (net (code "85") (name "unconnected-(IC106B-PM6-Pad72)") (class "Default")
      (node (ref "IC106") (pin "72") (pinfunction "PM6_72") (pintype "bidirectional"))
    )
    (net (code "86") (name "unconnected-(IC106B-PM7-Pad71)") (class "Default")
      (node (ref "IC106") (pin "71") (pinfunction "PM7_71") (pintype "bidirectional"))
    )
    (net (code "87") (name "unconnected-(IC106B-PN0-Pad107)") (class "Default")
      (node (ref "IC106") (pin "107") (pinfunction "PN0_107") (pintype "bidirectional"))
    )
    (net (code "88") (name "unconnected-(IC106B-PN1-Pad108)") (class "Default")
      (node (ref "IC106") (pin "108") (pinfunction "PN1_108") (pintype "bidirectional"))
    )
    (net (code "89") (name "unconnected-(IC106B-PN2-Pad109)") (class "Default")
      (node (ref "IC106") (pin "109") (pinfunction "PN2_109") (pintype "bidirectional"))
    )
    (net (code "90") (name "unconnected-(IC106B-PN3-Pad110)") (class "Default")
      (node (ref "IC106") (pin "110") (pinfunction "PN3_110") (pintype "bidirectional"))
    )
    (net (code "91") (name "unconnected-(IC106B-PN4-Pad111)") (class "Default")
      (node (ref "IC106") (pin "111") (pinfunction "PN4_111") (pintype "bidirectional"))
    )
    (net (code "92") (name "unconnected-(IC106B-PN5-Pad112)") (class "Default")
      (node (ref "IC106") (pin "112") (pinfunction "PN5_112") (pintype "bidirectional"))
    )
    (net (code "93") (name "unconnected-(IC106B-PP0-Pad118)") (class "Default")
      (node (ref "IC106") (pin "118") (pinfunction "PP0_118") (pintype "bidirectional"))
    )
    (net (code "94") (name "unconnected-(IC106B-PP1-Pad119)") (class "Default")
      (node (ref "IC106") (pin "119") (pinfunction "PP1_119") (pintype "bidirectional"))
    )
    (net (code "95") (name "unconnected-(IC106B-PP2-Pad103)") (class "Default")
      (node (ref "IC106") (pin "103") (pinfunction "PP2_103") (pintype "bidirectional"))
    )
    (net (code "96") (name "unconnected-(IC106B-PP3-Pad104)") (class "Default")
      (node (ref "IC106") (pin "104") (pinfunction "PP3_104") (pintype "bidirectional"))
    )
    (net (code "97") (name "unconnected-(IC106B-PP4-Pad105)") (class "Default")
      (node (ref "IC106") (pin "105") (pinfunction "PP4_105") (pintype "bidirectional"))
    )
    (net (code "98") (name "unconnected-(IC106B-PP5-Pad106)") (class "Default")
      (node (ref "IC106") (pin "106") (pinfunction "PP5_106") (pintype "bidirectional"))
    )
    (net (code "99") (name "unconnected-(IC106B-PQ0-Pad5)") (class "Default")
      (node (ref "IC106") (pin "5") (pinfunction "PQ0_5") (pintype "bidirectional"))
    )
    (net (code "100") (name "unconnected-(IC106B-PQ1-Pad6)") (class "Default")
      (node (ref "IC106") (pin "6") (pinfunction "PQ1_6") (pintype "bidirectional"))
    )
    (net (code "101") (name "unconnected-(IC106B-PQ2-Pad11)") (class "Default")
      (node (ref "IC106") (pin "11") (pinfunction "PQ2_11") (pintype "bidirectional"))
    )
    (net (code "102") (name "unconnected-(IC106B-PQ3-Pad27)") (class "Default")
      (node (ref "IC106") (pin "27") (pinfunction "PQ3_27") (pintype "bidirectional"))
    )
    (net (code "103") (name "unconnected-(IC106B-PQ4-Pad102)") (class "Default")
      (node (ref "IC106") (pin "102") (pinfunction "PQ4_102") (pintype "bidirectional"))
    )
    (net (code "104") (name "unconnected-(IC106C-EN0RXIN-Pad53)") (class "Default")
      (node (ref "IC106") (pin "53") (pinfunction "EN0RXIN_53") (pintype "bidirectional"))
    )
    (net (code "105") (name "unconnected-(IC106C-EN0RXIP-Pad54)") (class "Default")
      (node (ref "IC106") (pin "54") (pinfunction "EN0RXIP_54") (pintype "bidirectional"))
    )
    (net (code "106") (name "unconnected-(IC106C-EN0TXON-Pad56)") (class "Default")
      (node (ref "IC106") (pin "56") (pinfunction "EN0TXON_56") (pintype "bidirectional"))
    )
    (net (code "107") (name "unconnected-(IC106C-EN0TXOP-Pad57)") (class "Default")
      (node (ref "IC106") (pin "57") (pinfunction "EN0TXOP_57") (pintype "bidirectional"))
    )
    (net (code "108") (name "unconnected-(IC106C-HIB-Pad65)") (class "Default")
      (node (ref "IC106") (pin "65") (pinfunction "HIB_65") (pintype "output"))
    )
    (net (code "109") (name "unconnected-(IC106C-XOSC1-Pad67)") (class "Default")
      (node (ref "IC106") (pin "67") (pinfunction "XOSC1_67") (pintype "output"))
    )
    (net (code "110") (name "unconnected-(J108-Pad7)") (class "Default")
      (node (ref "J108") (pin "7") (pinfunction "7_7") (pintype "passive"))
    )
  )
)
